# power.net
KiCad netlist of a schematic drawn in EAGLE
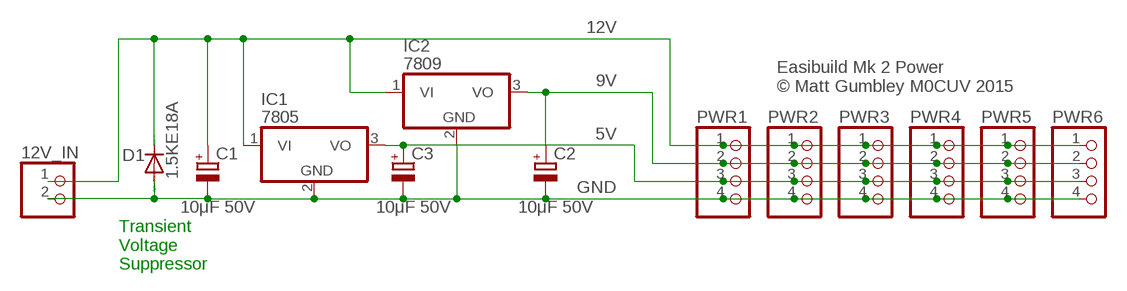
[diagram p0: schematic, sheet 1]

(export (version "E")
  (design (tool "Eeschema 10.0.6"))
  (components
    (comp (ref "12V_IN")
      (value "PINHD-1X2")
      (footprint "eagle-import:1X02")
      (libsource (lib "eagle-import") (part "PINHD-1X2"))
    )
    (comp (ref "C1")
      (value "10μF 50V")
      (footprint "eagle-import:E2,5-6E")
      (libsource (lib "eagle-import") (part "CPOL-EUE2,5-6E"))
    )
    (comp (ref "C2")
      (value "10μF 50V")
      (footprint "eagle-import:E2,5-6E")
      (libsource (lib "eagle-import") (part "CPOL-EUE2,5-6E"))
    )
    (comp (ref "C3")
      (value "10μF 50V")
      (footprint "eagle-import:E2,5-6E")
      (libsource (lib "eagle-import") (part "CPOL-EUE2,5-6E"))
    )
    (comp (ref "D1")
      (value "1.5KE18A")
      (footprint "eagle-import:C1702-254")
      (libsource (lib "eagle-import") (part "DIODE-2.54-VC1702-254"))
    )
    (comp (ref "IC1")
      (value "7805")
      (footprint "eagle-import:TO220V")
      (libsource (lib "eagle-import") (part "78TV05"))
    )
    (comp (ref "IC2")
      (value "7809")
      (footprint "eagle-import:TO220V")
      (libsource (lib "eagle-import") (part "78TV05"))
    )
    (comp (ref "PWR1")
      (value "PINHD-1X4")
      (footprint "eagle-import:1X04")
      (libsource (lib "eagle-import") (part "PINHD-1X4"))
    )
    (comp (ref "PWR2")
      (value "PINHD-1X4")
      (footprint "eagle-import:1X04")
      (libsource (lib "eagle-import") (part "PINHD-1X4"))
    )
    (comp (ref "PWR3")
      (value "PINHD-1X4")
      (footprint "eagle-import:1X04")
      (libsource (lib "eagle-import") (part "PINHD-1X4"))
    )
    (comp (ref "PWR4")
      (value "PINHD-1X4")
      (footprint "eagle-import:1X04")
      (libsource (lib "eagle-import") (part "PINHD-1X4"))
    )
    (comp (ref "PWR5")
      (value "PINHD-1X4")
      (footprint "eagle-import:1X04")
      (libsource (lib "eagle-import") (part "PINHD-1X4"))
    )
    (comp (ref "PWR6")
      (value "PINHD-1X4")
      (footprint "eagle-import:1X04")
      (libsource (lib "eagle-import") (part "PINHD-1X4"))
    )
  )
  (nets
    (net (code "1") (name "/5V") (class "Default")
      (node (ref "C3") (pin "+") (pinfunction "+_+") (pintype "passive"))
      (node (ref "IC1") (pin "3") (pinfunction "VO_3") (pintype "passive"))
      (node (ref "PWR1") (pin "3") (pinfunction "3_3") (pintype "passive"))
      (node (ref "PWR2") (pin "3") (pinfunction "3_3") (pintype "passive"))
      (node (ref "PWR3") (pin "3") (pinfunction "3_3") (pintype "passive"))
      (node (ref "PWR4") (pin "3") (pinfunction "3_3") (pintype "passive"))
      (node (ref "PWR5") (pin "3") (pinfunction "3_3") (pintype "passive"))
      (node (ref "PWR6") (pin "3") (pinfunction "3_3") (pintype "passive"))
    )
    (net (code "2") (name "/9V") (class "Default")
      (node (ref "C2") (pin "+") (pinfunction "+_+") (pintype "passive"))
      (node (ref "IC2") (pin "3") (pinfunction "VO_3") (pintype "passive"))
      (node (ref "PWR1") (pin "2") (pinfunction "2_2") (pintype "passive"))
      (node (ref "PWR2") (pin "2") (pinfunction "2_2") (pintype "passive"))
      (node (ref "PWR3") (pin "2") (pinfunction "2_2") (pintype "passive"))
      (node (ref "PWR4") (pin "2") (pinfunction "2_2") (pintype "passive"))
      (node (ref "PWR5") (pin "2") (pinfunction "2_2") (pintype "passive"))
      (node (ref "PWR6") (pin "2") (pinfunction "2_2") (pintype "passive"))
    )
    (net (code "3") (name "/12V") (class "Default")
      (node (ref "12V_IN") (pin "1") (pinfunction "1_1") (pintype "passive"))
      (node (ref "C1") (pin "+") (pinfunction "+_+") (pintype "passive"))
      (node (ref "D1") (pin "C") (pinfunction "C_C") (pintype "passive"))
      (node (ref "IC1") (pin "1") (pinfunction "VI_1") (pintype "input"))
      (node (ref "IC2") (pin "1") (pinfunction "VI_1") (pintype "input"))
      (node (ref "PWR1") (pin "1") (pinfunction "1_1") (pintype "passive"))
      (node (ref "PWR2") (pin "1") (pinfunction "1_1") (pintype "passive"))
      (node (ref "PWR3") (pin "1") (pinfunction "1_1") (pintype "passive"))
      (node (ref "PWR4") (pin "1") (pinfunction "1_1") (pintype "passive"))
      (node (ref "PWR5") (pin "1") (pinfunction "1_1") (pintype "passive"))
      (node (ref "PWR6") (pin "1") (pinfunction "1_1") (pintype "passive"))
    )
    (net (code "4") (name "/GND") (class "Default")
      (node (ref "12V_IN") (pin "2") (pinfunction "2_2") (pintype "passive"))
      (node (ref "C1") (pin "-") (pinfunction "-_-") (pintype "passive"))
      (node (ref "C2") (pin "-") (pinfunction "-_-") (pintype "passive"))
      (node (ref "C3") (pin "-") (pinfunction "-_-") (pintype "passive"))
      (node (ref "D1") (pin "A") (pinfunction "A_A") (pintype "passive"))
      (node (ref "IC1") (pin "2") (pinfunction "GND_2") (pintype "passive"))
      (node (ref "IC2") (pin "2") (pinfunction "GND_2") (pintype "passive"))
      (node (ref "PWR1") (pin "4") (pinfunction "4_4") (pintype "passive"))
      (node (ref "PWR2") (pin "4") (pinfunction "4_4") (pintype "passive"))
      (node (ref "PWR3") (pin "4") (pinfunction "4_4") (pintype "passive"))
      (node (ref "PWR4") (pin "4") (pinfunction "4_4") (pintype "passive"))
      (node (ref "PWR5") (pin "4") (pinfunction "4_4") (pintype "passive"))
      (node (ref "PWR6") (pin "4") (pinfunction "4_4") (pintype "passive"))
    )
  )
)
